# hardware.net
KiCad netlist of a schematic drawn in Altium Designer
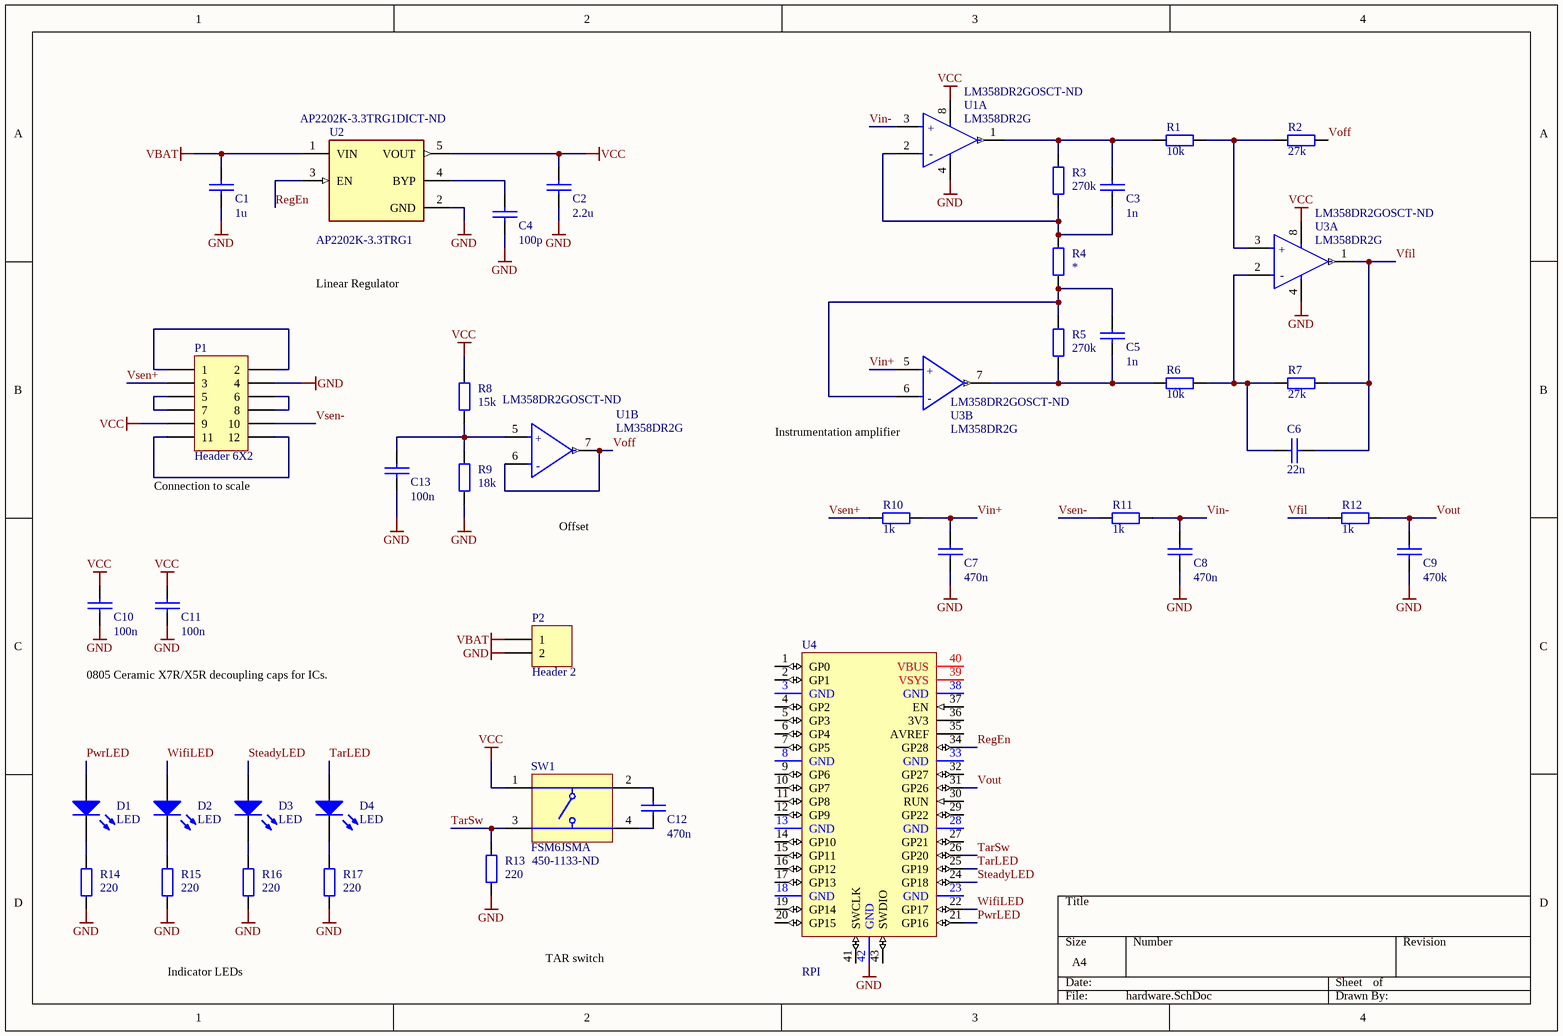
[diagram p0: hardware.SchDoc]

(export (version "E")
  (design (tool "Eeschema 10.0.6"))
  (components
    (comp (ref "C1")
      (value "1u")
      (footprint "EE311_footprints:C0805")
      (description "CCAP0805")
      (libsource (lib "EE311_symbols") (part "CCAP0805"))
    )
    (comp (ref "C2")
      (value "2.2u")
      (footprint "EE311_footprints:C0805")
      (description "CCAP0805")
      (libsource (lib "EE311_symbols") (part "CCAP0805"))
    )
    (comp (ref "C3")
      (value "1n")
      (footprint "EE311_footprints:C0805")
      (description "CCAP0805")
      (libsource (lib "EE311_symbols") (part "CCAP0805"))
    )
    (comp (ref "C4")
      (value "100p")
      (footprint "EE311_footprints:C0805")
      (description "CCAP0805")
      (libsource (lib "EE311_symbols") (part "CCAP0805"))
    )
    (comp (ref "C5")
      (value "1n")
      (footprint "EE311_footprints:C0805")
      (description "CCAP0805")
      (libsource (lib "EE311_symbols") (part "CCAP0805"))
    )
    (comp (ref "C6")
      (value "22n")
      (footprint "EE311_footprints:C0805")
      (description "CCAP0805")
      (libsource (lib "EE311_symbols") (part "CCAP0805"))
    )
    (comp (ref "C7")
      (value "470n")
      (footprint "EE311_footprints:C0805")
      (description "CCAP0805")
      (libsource (lib "EE311_symbols") (part "CCAP0805"))
    )
    (comp (ref "C8")
      (value "470n")
      (footprint "EE311_footprints:C0805")
      (description "CCAP0805")
      (libsource (lib "EE311_symbols") (part "CCAP0805"))
    )
    (comp (ref "C9")
      (value "470k")
      (footprint "EE311_footprints:C0805")
      (description "CCAP0805")
      (libsource (lib "EE311_symbols") (part "CCAP0805"))
    )
    (comp (ref "C10")
      (value "100n")
      (footprint "EE311_footprints:C0805")
      (description "CCAP0805")
      (libsource (lib "EE311_symbols") (part "CCAP0805"))
    )
    (comp (ref "C11")
      (value "100n")
      (footprint "EE311_footprints:C0805")
      (description "CCAP0805")
      (libsource (lib "EE311_symbols") (part "CCAP0805"))
    )
    (comp (ref "C12")
      (value "470n")
      (footprint "EE311_footprints:C0805")
      (description "CCAP0805")
      (libsource (lib "EE311_symbols") (part "CCAP0805"))
    )
    (comp (ref "C13")
      (value "100n")
      (footprint "EE311_footprints:C0805")
      (description "CCAP0805")
      (libsource (lib "EE311_symbols") (part "CCAP0805"))
    )
    (comp (ref "D1")
      (value "LED")
      (footprint "EE311_footprints:LED0805")
      (libsource (lib "EE311_symbols") (part "LED"))
    )
    (comp (ref "D2")
      (value "LED")
      (footprint "EE311_footprints:LED0805")
      (libsource (lib "EE311_symbols") (part "LED"))
    )
    (comp (ref "D3")
      (value "LED")
      (footprint "EE311_footprints:LED0805")
      (libsource (lib "EE311_symbols") (part "LED"))
    )
    (comp (ref "D4")
      (value "LED")
      (footprint "EE311_footprints:LED0805")
      (libsource (lib "EE311_symbols") (part "LED"))
    )
    (comp (ref "P1")
      (value "Header 6X2")
      (footprint "HDR2X6")
      (description "Header, 6-Pin, Dual row")
      (fields (field (name "PUBLISHER") "Altium Limited"))
      (libsource (lib "Miscellaneous Connectors") (part "Header 6X2"))
    )
    (comp (ref "P2")
      (value "Header 2")
      (footprint "HDR1X2")
      (description "Header, 2-Pin")
      (fields (field (name "PUBLISHER") "Altium Limited"))
      (libsource (lib "Miscellaneous Connectors") (part "Header 2"))
    )
    (comp (ref "R1")
      (value "10k")
      (footprint "R0805")
      (description "RES0805")
      (libsource (lib "") (part "RES0805_1"))
    )
    (comp (ref "R2")
      (value "27k")
      (footprint "R0805")
      (description "RES0805")
      (libsource (lib "") (part "RES0805_1"))
    )
    (comp (ref "R3")
      (value "270k")
      (footprint "R0805")
      (description "RES0805")
      (libsource (lib "EE311_symbols") (part "RES0805"))
    )
    (comp (ref "R4")
      (value "*")
      (footprint "R0805")
      (description "RES0805")
      (libsource (lib "EE311_symbols") (part "RES0805"))
    )
    (comp (ref "R5")
      (value "270k")
      (footprint "R0805")
      (description "RES0805")
      (libsource (lib "EE311_symbols") (part "RES0805"))
    )
    (comp (ref "R6")
      (value "10k")
      (footprint "R0805")
      (description "RES0805")
      (libsource (lib "") (part "RES0805_1"))
    )
    (comp (ref "R7")
      (value "27k")
      (footprint "R0805")
      (description "RES0805")
      (libsource (lib "") (part "RES0805_1"))
    )
    (comp (ref "R8")
      (value "15k")
      (footprint "R0805")
      (description "RES0805")
      (libsource (lib "EE311_symbols") (part "RES0805"))
    )
    (comp (ref "R9")
      (value "18k")
      (footprint "R0805")
      (description "RES0805")
      (libsource (lib "EE311_symbols") (part "RES0805"))
    )
    (comp (ref "R10")
      (value "1k")
      (footprint "R0805")
      (description "RES0805")
      (libsource (lib "") (part "RES0805_1"))
    )
    (comp (ref "R11")
      (value "1k")
      (footprint "R0805")
      (description "RES0805")
      (libsource (lib "") (part "RES0805_1"))
    )
    (comp (ref "R12")
      (value "1k")
      (footprint "R0805")
      (description "RES0805")
      (libsource (lib "") (part "RES0805_1"))
    )
    (comp (ref "R13")
      (value "220")
      (footprint "R0805")
      (description "RES0805")
      (libsource (lib "EE311_symbols") (part "RES0805"))
    )
    (comp (ref "R14")
      (value "220")
      (footprint "R0805")
      (description "RES0805")
      (libsource (lib "EE311_symbols") (part "RES0805"))
    )
    (comp (ref "R15")
      (value "220")
      (footprint "R0805")
      (description "RES0805")
      (libsource (lib "EE311_symbols") (part "RES0805"))
    )
    (comp (ref "R16")
      (value "220")
      (footprint "R0805")
      (description "RES0805")
      (libsource (lib "EE311_symbols") (part "RES0805"))
    )
    (comp (ref "R17")
      (value "220")
      (footprint "R0805")
      (description "RES0805")
      (libsource (lib "EE311_symbols") (part "RES0805"))
    )
    (comp (ref "SW1")
      (value "FSM6JSMA")
      (footprint "TECO-FSM6JSMA_V")
      (description "Switch, SPST, 24 V, -35 to 85 degC, 4-Pin SMD, RoHS, Tape and Reel")
      (fields
        (field (name "MANUFACTURER") "TE Connectivity")
        (field (name "SUPPLIER PART NUMBER 1") "450-1133-ND")
      )
      (libsource (lib "Altium Content Vault") (part "SW-SPST-4_A"))
    )
    (comp (ref "U1")
      (value "LM358DR2G")
      (footprint "FP-751-07-IPC_C")
      (description "IC OPAMP GP 2 CIRCUIT 8SOIC")
      (fields
        (field (name "SUPPLIER PART NUMBER 1") "LM358DR2GOSCT-ND")
        (field (name "MANUFACTURER") "ON Semiconductor")
      )
      (libsource (lib "Altium Content Vault") (part "992a6607d1d88c80ee6b45e5ba6cb1b"))
    )
    (comp (ref "U2")
      (value "AP2202K-3.3TRG1")
      (footprint "FP-SOT25-MFG")
      (description "IC REG LINEAR 3.3V 150MA SOT23-5")
      (fields
        (field (name "OCTOPART") "https://octopart.com/ap2202k-3.3trg1-diodes+inc.-30954618")
        (field (name "MANUFACTURER") "Diodes Inc.")
        (field (name "SUPPLIER PART NUMBER 1") "AP2202K-3.3TRG1DICT-ND")
      )
      (libsource (lib "Altium Content Vault") (part "006e7a011770a62fb00db70566099d5"))
    )
    (comp (ref "U3")
      (value "LM358DR2G")
      (footprint "FP-751-07-IPC_C")
      (description "IC OPAMP GP 2 CIRCUIT 8SOIC")
      (fields
        (field (name "SUPPLIER PART NUMBER 1") "LM358DR2GOSCT-ND")
        (field (name "MANUFACTURER") "ON Semiconductor")
      )
      (libsource (lib "Altium Content Vault") (part "992a6607d1d88c80ee6b45e5ba6cb1b"))
    )
    (comp (ref "U4") (value "RPI") (footprint "RPI-PICO-MOD") (libsource (lib "EE311_symbols") (part "RPI")))
  )
  (nets
    (net (code "1") (name "/PwrLED") (class "Default")
      (node (ref "D1") (pin "1") (pinfunction "A_1") (pintype "passive"))
      (node (ref "U4") (pin "21") (pinfunction "GP16_21") (pintype "bidirectional"))
    )
    (net (code "2") (name "/RegEn") (class "Default")
      (node (ref "U2") (pin "3") (pinfunction "EN_3") (pintype "input"))
      (node (ref "U4") (pin "34") (pinfunction "GP28_34") (pintype "bidirectional"))
    )
    (net (code "3") (name "/SteadyLED") (class "Default")
      (node (ref "D3") (pin "1") (pinfunction "A_1") (pintype "passive"))
      (node (ref "U4") (pin "24") (pinfunction "GP18_24") (pintype "bidirectional"))
    )
    (net (code "4") (name "/TarLED") (class "Default")
      (node (ref "D4") (pin "1") (pinfunction "A_1") (pintype "passive"))
      (node (ref "U4") (pin "25") (pinfunction "GP19_25") (pintype "bidirectional"))
    )
    (net (code "5") (name "/TarSw") (class "Default")
      (node (ref "R13") (pin "2") (pinfunction "2_2") (pintype "passive"))
      (node (ref "SW1") (pin "3") (pinfunction "3_3") (pintype "passive"))
      (node (ref "U4") (pin "26") (pinfunction "GP20_26") (pintype "bidirectional"))
    )
    (net (code "6") (name "/Vfil") (class "Default")
      (node (ref "C6") (pin "1") (pinfunction "1_1") (pintype "passive"))
      (node (ref "R12") (pin "2") (pinfunction "2_2") (pintype "passive"))
      (node (ref "R7") (pin "1") (pinfunction "1_1") (pintype "passive"))
      (node (ref "U3") (pin "1") (pinfunction "OUTPUT_A_1") (pintype "output"))
    )
    (net (code "7") (name "/Vin+") (class "Default")
      (node (ref "C7") (pin "2") (pinfunction "2_2") (pintype "passive"))
      (node (ref "R10") (pin "1") (pinfunction "1_1") (pintype "passive"))
      (node (ref "U3") (pin "5") (pinfunction "INPUT_B+_5") (pintype "tri_state"))
    )
    (net (code "8") (name "/Vin-") (class "Default")
      (node (ref "C8") (pin "2") (pinfunction "2_2") (pintype "passive"))
      (node (ref "R11") (pin "1") (pinfunction "1_1") (pintype "passive"))
      (node (ref "U1") (pin "3") (pinfunction "INPUT_A+_3") (pintype "tri_state"))
    )
    (net (code "9") (name "/Voff") (class "Default")
      (node (ref "R2") (pin "1") (pinfunction "1_1") (pintype "passive"))
      (node (ref "U1") (pin "6") (pinfunction "INPUT_B-_6") (pintype "tri_state"))
      (node (ref "U1") (pin "7") (pinfunction "OUTPUT_B_7") (pintype "output"))
    )
    (net (code "10") (name "/Vout") (class "Default")
      (node (ref "C9") (pin "2") (pinfunction "2_2") (pintype "passive"))
      (node (ref "R12") (pin "1") (pinfunction "1_1") (pintype "passive"))
      (node (ref "U4") (pin "31") (pinfunction "GP26_31") (pintype "bidirectional"))
    )
    (net (code "11") (name "/Vsen+") (class "Default")
      (node (ref "P1") (pin "3") (pinfunction "3_3") (pintype "passive"))
      (node (ref "R10") (pin "2") (pinfunction "2_2") (pintype "passive"))
    )
    (net (code "12") (name "/Vsen-") (class "Default")
      (node (ref "P1") (pin "10") (pinfunction "10_10") (pintype "passive"))
      (node (ref "R11") (pin "2") (pinfunction "2_2") (pintype "passive"))
    )
    (net (code "13") (name "/WifiLED") (class "Default")
      (node (ref "D2") (pin "1") (pinfunction "A_1") (pintype "passive"))
      (node (ref "U4") (pin "22") (pinfunction "GP17_22") (pintype "bidirectional"))
    )
    (net (code "14") (name "GND") (class "Default")
      (node (ref "C1") (pin "1") (pinfunction "1_1") (pintype "passive"))
      (node (ref "C10") (pin "1") (pinfunction "1_1") (pintype "passive"))
      (node (ref "C11") (pin "1") (pinfunction "1_1") (pintype "passive"))
      (node (ref "C13") (pin "1") (pinfunction "1_1") (pintype "passive"))
      (node (ref "C2") (pin "1") (pinfunction "1_1") (pintype "passive"))
      (node (ref "C4") (pin "1") (pinfunction "1_1") (pintype "passive"))
      (node (ref "C7") (pin "1") (pinfunction "1_1") (pintype "passive"))
      (node (ref "C8") (pin "1") (pinfunction "1_1") (pintype "passive"))
      (node (ref "C9") (pin "1") (pinfunction "1_1") (pintype "passive"))
      (node (ref "P1") (pin "4") (pinfunction "4_4") (pintype "passive"))
      (node (ref "P2") (pin "2") (pinfunction "2_2") (pintype "passive"))
      (node (ref "R13") (pin "1") (pinfunction "1_1") (pintype "passive"))
      (node (ref "R14") (pin "1") (pinfunction "1_1") (pintype "passive"))
      (node (ref "R15") (pin "1") (pinfunction "1_1") (pintype "passive"))
      (node (ref "R16") (pin "1") (pinfunction "1_1") (pintype "passive"))
      (node (ref "R17") (pin "1") (pinfunction "1_1") (pintype "passive"))
      (node (ref "R9") (pin "1") (pinfunction "1_1") (pintype "passive"))
      (node (ref "U1") (pin "4") (pinfunction "VEE/GND_4") (pintype "power_in"))
      (node (ref "U2") (pin "2") (pinfunction "GND_2") (pintype "power_in"))
      (node (ref "U3") (pin "4") (pinfunction "VEE/GND_4") (pintype "power_in"))
      (node (ref "U4") (pin "42") (pinfunction "GND_42") (pintype "power_in"))
    )
    (net (code "15") (name "Net-(C12-Pad1)") (class "Default")
      (node (ref "C12") (pin "1") (pinfunction "1_1") (pintype "passive"))
      (node (ref "SW1") (pin "4") (pinfunction "4_4") (pintype "passive"))
    )
    (net (code "16") (name "Net-(C12-Pad2)") (class "Default")
      (node (ref "C12") (pin "2") (pinfunction "2_2") (pintype "passive"))
      (node (ref "SW1") (pin "2") (pinfunction "2_2") (pintype "passive"))
    )
    (net (code "17") (name "Net-(D1-K)") (class "Default")
      (node (ref "D1") (pin "2") (pinfunction "K_2") (pintype "passive"))
      (node (ref "R14") (pin "2") (pinfunction "2_2") (pintype "passive"))
    )
    (net (code "18") (name "Net-(D2-K)") (class "Default")
      (node (ref "D2") (pin "2") (pinfunction "K_2") (pintype "passive"))
      (node (ref "R15") (pin "2") (pinfunction "2_2") (pintype "passive"))
    )
    (net (code "19") (name "Net-(D3-K)") (class "Default")
      (node (ref "D3") (pin "2") (pinfunction "K_2") (pintype "passive"))
      (node (ref "R16") (pin "2") (pinfunction "2_2") (pintype "passive"))
    )
    (net (code "20") (name "Net-(D4-K)") (class "Default")
      (node (ref "D4") (pin "2") (pinfunction "K_2") (pintype "passive"))
      (node (ref "R17") (pin "2") (pinfunction "2_2") (pintype "passive"))
    )
    (net (code "21") (name "Net-(P1-Pad1)") (class "Default")
      (node (ref "P1") (pin "1") (pinfunction "1_1") (pintype "passive"))
      (node (ref "P1") (pin "2") (pinfunction "2_2") (pintype "passive"))
    )
    (net (code "22") (name "Net-(P1-Pad5)") (class "Default")
      (node (ref "P1") (pin "5") (pinfunction "5_5") (pintype "passive"))
      (node (ref "P1") (pin "7") (pinfunction "7_7") (pintype "passive"))
    )
    (net (code "23") (name "Net-(P1-Pad6)") (class "Default")
      (node (ref "P1") (pin "6") (pinfunction "6_6") (pintype "passive"))
      (node (ref "P1") (pin "8") (pinfunction "8_8") (pintype "passive"))
    )
    (net (code "24") (name "Net-(P1-Pad11)") (class "Default")
      (node (ref "P1") (pin "11") (pinfunction "11_11") (pintype "passive"))
      (node (ref "P1") (pin "12") (pinfunction "12_12") (pintype "passive"))
    )
    (net (code "25") (name "Net-(U1A-INPUT_A-)") (class "Default")
      (node (ref "C3") (pin "1") (pinfunction "1_1") (pintype "passive"))
      (node (ref "R3") (pin "1") (pinfunction "1_1") (pintype "passive"))
      (node (ref "R4") (pin "2") (pinfunction "2_2") (pintype "passive"))
      (node (ref "U1") (pin "2") (pinfunction "INPUT_A-_2") (pintype "tri_state"))
    )
    (net (code "26") (name "Net-(U1A-OUTPUT_A)") (class "Default")
      (node (ref "C3") (pin "2") (pinfunction "2_2") (pintype "passive"))
      (node (ref "R1") (pin "2") (pinfunction "2_2") (pintype "passive"))
      (node (ref "R3") (pin "2") (pinfunction "2_2") (pintype "passive"))
      (node (ref "U1") (pin "1") (pinfunction "OUTPUT_A_1") (pintype "output"))
    )
    (net (code "27") (name "Net-(U1B-INPUT_B+)") (class "Default")
      (node (ref "C13") (pin "2") (pinfunction "2_2") (pintype "passive"))
      (node (ref "R8") (pin "1") (pinfunction "1_1") (pintype "passive"))
      (node (ref "R9") (pin "2") (pinfunction "2_2") (pintype "passive"))
      (node (ref "U1") (pin "5") (pinfunction "INPUT_B+_5") (pintype "tri_state"))
    )
    (net (code "28") (name "Net-(U2-BYP)") (class "Default")
      (node (ref "C4") (pin "2") (pinfunction "2_2") (pintype "passive"))
      (node (ref "U2") (pin "4") (pinfunction "BYP_4") (pintype "passive"))
    )
    (net (code "29") (name "Net-(U3A-INPUT_A+)") (class "Default")
      (node (ref "R1") (pin "1") (pinfunction "1_1") (pintype "passive"))
      (node (ref "R2") (pin "2") (pinfunction "2_2") (pintype "passive"))
      (node (ref "U3") (pin "3") (pinfunction "INPUT_A+_3") (pintype "tri_state"))
    )
    (net (code "30") (name "Net-(U3A-INPUT_A-)") (class "Default")
      (node (ref "C6") (pin "2") (pinfunction "2_2") (pintype "passive"))
      (node (ref "R6") (pin "1") (pinfunction "1_1") (pintype "passive"))
      (node (ref "R7") (pin "2") (pinfunction "2_2") (pintype "passive"))
      (node (ref "U3") (pin "2") (pinfunction "INPUT_A-_2") (pintype "tri_state"))
    )
    (net (code "31") (name "Net-(U3B-INPUT_B-)") (class "Default")
      (node (ref "C5") (pin "2") (pinfunction "2_2") (pintype "passive"))
      (node (ref "R4") (pin "1") (pinfunction "1_1") (pintype "passive"))
      (node (ref "R5") (pin "2") (pinfunction "2_2") (pintype "passive"))
      (node (ref "U3") (pin "6") (pinfunction "INPUT_B-_6") (pintype "tri_state"))
    )
    (net (code "32") (name "Net-(U3B-OUTPUT_B)") (class "Default")
      (node (ref "C5") (pin "1") (pinfunction "1_1") (pintype "passive"))
      (node (ref "R5") (pin "1") (pinfunction "1_1") (pintype "passive"))
      (node (ref "R6") (pin "2") (pinfunction "2_2") (pintype "passive"))
      (node (ref "U3") (pin "7") (pinfunction "OUTPUT_B_7") (pintype "output"))
    )
    (net (code "33") (name "VBAT") (class "Default")
      (node (ref "C1") (pin "2") (pinfunction "2_2") (pintype "passive"))
      (node (ref "P2") (pin "1") (pinfunction "1_1") (pintype "passive"))
      (node (ref "U2") (pin "1") (pinfunction "VIN_1") (pintype "power_in"))
    )
    (net (code "34") (name "VCC") (class "Default")
      (node (ref "C10") (pin "2") (pinfunction "2_2") (pintype "passive"))
      (node (ref "C11") (pin "2") (pinfunction "2_2") (pintype "passive"))
      (node (ref "C2") (pin "2") (pinfunction "2_2") (pintype "passive"))
      (node (ref "P1") (pin "9") (pinfunction "9_9") (pintype "passive"))
      (node (ref "R8") (pin "2") (pinfunction "2_2") (pintype "passive"))
      (node (ref "SW1") (pin "1") (pinfunction "1_1") (pintype "passive"))
      (node (ref "U1") (pin "8") (pinfunction "VCC_8") (pintype "power_in"))
      (node (ref "U2") (pin "5") (pinfunction "VOUT_5") (pintype "output"))
      (node (ref "U3") (pin "8") (pinfunction "VCC_8") (pintype "power_in"))
    )
    (net (code "35") (name "unconnected-(U4-3V3-Pad36)") (class "Default")
      (node (ref "U4") (pin "36") (pinfunction "3V3_36") (pintype "power_in"))
    )
    (net (code "36") (name "unconnected-(U4-AVREF-Pad35)") (class "Default")
      (node (ref "U4") (pin "35") (pinfunction "AVREF_35") (pintype "power_in"))
    )
    (net (code "37") (name "unconnected-(U4-EN-Pad37)") (class "Default")
      (node (ref "U4") (pin "37") (pinfunction "EN_37") (pintype "input"))
    )
    (net (code "38") (name "unconnected-(U4-GND-Pad3)") (class "Default")
      (node (ref "U4") (pin "3") (pinfunction "GND_3") (pintype "power_in"))
    )
    (net (code "39") (name "unconnected-(U4-GND-Pad8)") (class "Default")
      (node (ref "U4") (pin "8") (pinfunction "GND_8") (pintype "power_in"))
    )
    (net (code "40") (name "unconnected-(U4-GND-Pad13)") (class "Default")
      (node (ref "U4") (pin "13") (pinfunction "GND_13") (pintype "power_in"))
    )
    (net (code "41") (name "unconnected-(U4-GND-Pad18)") (class "Default")
      (node (ref "U4") (pin "18") (pinfunction "GND_18") (pintype "power_in"))
    )
    (net (code "42") (name "unconnected-(U4-GND-Pad23)") (class "Default")
      (node (ref "U4") (pin "23") (pinfunction "GND_23") (pintype "power_in"))
    )
    (net (code "43") (name "unconnected-(U4-GND-Pad28)") (class "Default")
      (node (ref "U4") (pin "28") (pinfunction "GND_28") (pintype "power_in"))
    )
    (net (code "44") (name "unconnected-(U4-GND-Pad33)") (class "Default")
      (node (ref "U4") (pin "33") (pinfunction "GND_33") (pintype "power_in"))
    )
    (net (code "45") (name "unconnected-(U4-GND-Pad38)") (class "Default")
      (node (ref "U4") (pin "38") (pinfunction "GND_38") (pintype "power_in"))
    )
    (net (code "46") (name "unconnected-(U4-GP0-Pad1)") (class "Default")
      (node (ref "U4") (pin "1") (pinfunction "GP0_1") (pintype "bidirectional"))
    )
    (net (code "47") (name "unconnected-(U4-GP1-Pad2)") (class "Default")
      (node (ref "U4") (pin "2") (pinfunction "GP1_2") (pintype "bidirectional"))
    )
    (net (code "48") (name "unconnected-(U4-GP2-Pad4)") (class "Default")
      (node (ref "U4") (pin "4") (pinfunction "GP2_4") (pintype "bidirectional"))
    )
    (net (code "49") (name "unconnected-(U4-GP3-Pad5)") (class "Default")
      (node (ref "U4") (pin "5") (pinfunction "GP3_5") (pintype "bidirectional"))
    )
    (net (code "50") (name "unconnected-(U4-GP4-Pad6)") (class "Default")
      (node (ref "U4") (pin "6") (pinfunction "GP4_6") (pintype "bidirectional"))
    )
    (net (code "51") (name "unconnected-(U4-GP5-Pad7)") (class "Default")
      (node (ref "U4") (pin "7") (pinfunction "GP5_7") (pintype "bidirectional"))
    )
    (net (code "52") (name "unconnected-(U4-GP6-Pad9)") (class "Default")
      (node (ref "U4") (pin "9") (pinfunction "GP6_9") (pintype "bidirectional"))
    )
    (net (code "53") (name "unconnected-(U4-GP7-Pad10)") (class "Default")
      (node (ref "U4") (pin "10") (pinfunction "GP7_10") (pintype "bidirectional"))
    )
    (net (code "54") (name "unconnected-(U4-GP8-Pad11)") (class "Default")
      (node (ref "U4") (pin "11") (pinfunction "GP8_11") (pintype "bidirectional"))
    )
    (net (code "55") (name "unconnected-(U4-GP9-Pad12)") (class "Default")
      (node (ref "U4") (pin "12") (pinfunction "GP9_12") (pintype "bidirectional"))
    )
    (net (code "56") (name "unconnected-(U4-GP10-Pad14)") (class "Default")
      (node (ref "U4") (pin "14") (pinfunction "GP10_14") (pintype "bidirectional"))
    )
    (net (code "57") (name "unconnected-(U4-GP11-Pad15)") (class "Default")
      (node (ref "U4") (pin "15") (pinfunction "GP11_15") (pintype "bidirectional"))
    )
    (net (code "58") (name "unconnected-(U4-GP12-Pad16)") (class "Default")
      (node (ref "U4") (pin "16") (pinfunction "GP12_16") (pintype "bidirectional"))
    )
    (net (code "59") (name "unconnected-(U4-GP13-Pad17)") (class "Default")
      (node (ref "U4") (pin "17") (pinfunction "GP13_17") (pintype "bidirectional"))
    )
    (net (code "60") (name "unconnected-(U4-GP14-Pad19)") (class "Default")
      (node (ref "U4") (pin "19") (pinfunction "GP14_19") (pintype "bidirectional"))
    )
    (net (code "61") (name "unconnected-(U4-GP15-Pad20)") (class "Default")
      (node (ref "U4") (pin "20") (pinfunction "GP15_20") (pintype "bidirectional"))
    )
    (net (code "62") (name "unconnected-(U4-GP21-Pad27)") (class "Default")
      (node (ref "U4") (pin "27") (pinfunction "GP21_27") (pintype "bidirectional"))
    )
    (net (code "63") (name "unconnected-(U4-GP22-Pad29)") (class "Default")
      (node (ref "U4") (pin "29") (pinfunction "GP22_29") (pintype "bidirectional"))
    )
    (net (code "64") (name "unconnected-(U4-GP27-Pad32)") (class "Default")
      (node (ref "U4") (pin "32") (pinfunction "GP27_32") (pintype "bidirectional"))
    )
    (net (code "65") (name "unconnected-(U4-RUN-Pad30)") (class "Default")
      (node (ref "U4") (pin "30") (pinfunction "RUN_30") (pintype "input"))
    )
    (net (code "66") (name "unconnected-(U4-SWCLK-Pad41)") (class "Default")
      (node (ref "U4") (pin "41") (pinfunction "SWCLK_41") (pintype "bidirectional"))
    )
    (net (code "67") (name "unconnected-(U4-SWDIO-Pad43)") (class "Default")
      (node (ref "U4") (pin "43") (pinfunction "SWDIO_43") (pintype "bidirectional"))
    )
    (net (code "68") (name "unconnected-(U4-VBUS-Pad40)") (class "Default")
      (node (ref "U4") (pin "40") (pinfunction "VBUS_40") (pintype "power_in"))
    )
    (net (code "69") (name "unconnected-(U4-VSYS-Pad39)") (class "Default")
      (node (ref "U4") (pin "39") (pinfunction "VSYS_39") (pintype "power_in"))
    )
  )
)
